# untitled.net
KiCad netlist of a schematic drawn in EAGLE
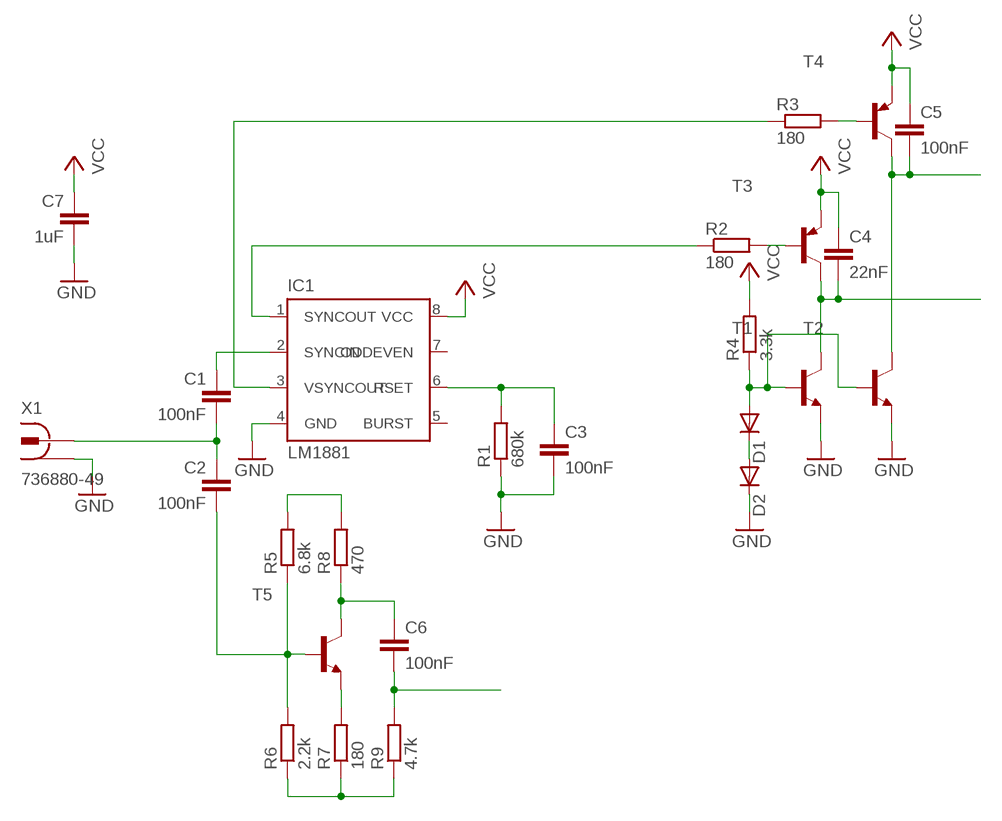
[diagram p0: schematic, sheet 1]

(export (version "E")
  (design (tool "Eeschema 10.0.6"))
  (components
    (comp (ref "C1")
      (value "100nF")
      (footprint "eagle-import:C0805")
      (libsource (lib "eagle-import") (part "C-EUC0805"))
    )
    (comp (ref "C2")
      (value "100nF")
      (footprint "eagle-import:C0805")
      (libsource (lib "eagle-import") (part "C-EUC0805"))
    )
    (comp (ref "C3")
      (value "100nF")
      (footprint "eagle-import:C0805")
      (libsource (lib "eagle-import") (part "C-EUC0805"))
    )
    (comp (ref "C4")
      (value "22nF")
      (footprint "eagle-import:C0805")
      (libsource (lib "eagle-import") (part "C-EUC0805"))
    )
    (comp (ref "C5")
      (value "100nF")
      (footprint "eagle-import:C0805")
      (libsource (lib "eagle-import") (part "C-EUC0805"))
    )
    (comp (ref "C6")
      (value "100nF")
      (footprint "eagle-import:C0805")
      (libsource (lib "eagle-import") (part "C-EUC0805"))
    )
    (comp (ref "C7")
      (value "1uF")
      (footprint "eagle-import:C0805")
      (libsource (lib "eagle-import") (part "C-EUC0805"))
    )
    (comp (ref "D1")
      (value "DIODE-MELF-MLL41")
      (footprint "eagle-import:MELF-MLL41")
      (libsource (lib "eagle-import") (part "DIODE-MELF-MLL41"))
    )
    (comp (ref "D2")
      (value "DIODE-MELF-MLL41")
      (footprint "eagle-import:MELF-MLL41")
      (libsource (lib "eagle-import") (part "DIODE-MELF-MLL41"))
    )
    (comp (ref "IC1")
      (value "LM1881")
      (footprint "eagle-import:DIL08")
      (libsource (lib "eagle-import") (part "LM1881"))
    )
    (comp (ref "R1")
      (value "680k")
      (footprint "eagle-import:R0805")
      (libsource (lib "eagle-import") (part "R-EU_R0805"))
    )
    (comp (ref "R2")
      (value "180")
      (footprint "eagle-import:R0805")
      (libsource (lib "eagle-import") (part "R-EU_R0805"))
    )
    (comp (ref "R3")
      (value "180")
      (footprint "eagle-import:R0805")
      (libsource (lib "eagle-import") (part "R-EU_R0805"))
    )
    (comp (ref "R4")
      (value "3.3k")
      (footprint "eagle-import:R0805")
      (libsource (lib "eagle-import") (part "R-EU_R0805"))
    )
    (comp (ref "R5")
      (value "6.8k")
      (footprint "eagle-import:R0805")
      (libsource (lib "eagle-import") (part "R-EU_R0805"))
    )
    (comp (ref "R6")
      (value "2.2k")
      (footprint "eagle-import:R0805")
      (libsource (lib "eagle-import") (part "R-EU_R0805"))
    )
    (comp (ref "R7")
      (value "180")
      (footprint "eagle-import:R0805")
      (libsource (lib "eagle-import") (part "R-EU_R0805"))
    )
    (comp (ref "R8")
      (value "470")
      (footprint "eagle-import:R0805")
      (libsource (lib "eagle-import") (part "R-EU_R0805"))
    )
    (comp (ref "R9")
      (value "4.7k")
      (footprint "eagle-import:R0805")
      (libsource (lib "eagle-import") (part "R-EU_R0805"))
    )
    (comp (ref "T1")
      (value "-NPN-SOT23-EBC")
      (footprint "eagle-import:SOT23-EBC")
      (libsource (lib "eagle-import") (part "-NPN-SOT23-EBC"))
    )
    (comp (ref "T2")
      (value "-NPN-SOT23-EBC")
      (footprint "eagle-import:SOT23-EBC")
      (libsource (lib "eagle-import") (part "-NPN-SOT23-EBC"))
    )
    (comp (ref "T3")
      (value "-PNP-SOT23-BCE")
      (footprint "eagle-import:SOT23-BCE")
      (libsource (lib "eagle-import") (part "-PNP-SOT23-BCE"))
    )
    (comp (ref "T4")
      (value "-PNP-SOT23-BCE")
      (footprint "eagle-import:SOT23-BCE")
      (libsource (lib "eagle-import") (part "-PNP-SOT23-BCE"))
    )
    (comp (ref "T5")
      (value "-NPN-SOT23-EBC")
      (footprint "eagle-import:SOT23-EBC")
      (libsource (lib "eagle-import") (part "-NPN-SOT23-EBC"))
    )
    (comp (ref "X1")
      (value "736880-49")
      (footprint "eagle-import:736880-49")
      (libsource (lib "eagle-import") (part "736880-49"))
    )
  )
  (nets
    (net (code "1") (name "GND") (class "Default")
      (node (ref "C3") (pin "2") (pinfunction "2_2") (pintype "passive"))
      (node (ref "C7") (pin "2") (pinfunction "2_2") (pintype "passive"))
      (node (ref "D2") (pin "C") (pinfunction "C_C") (pintype "passive"))
      (node (ref "IC1") (pin "4") (pinfunction "GND_4") (pintype "power_in"))
      (node (ref "R1") (pin "1") (pinfunction "1_1") (pintype "passive"))
      (node (ref "T1") (pin "E") (pinfunction "E_E") (pintype "passive"))
      (node (ref "T2") (pin "E") (pinfunction "E_E") (pintype "passive"))
      (node (ref "X1") (pin "1") (pinfunction "1_1") (pintype "passive"))
      (node (ref "X1") (pin "1@1") (pinfunction "1_1@1") (pintype "passive"))
      (node (ref "X1") (pin "1@2") (pinfunction "1_1@2") (pintype "passive"))
    )
    (net (code "2") (name "Net-(C1-Pad2)") (class "Default")
      (node (ref "C1") (pin "2") (pinfunction "2_2") (pintype "passive"))
      (node (ref "C2") (pin "1") (pinfunction "1_1") (pintype "passive"))
      (node (ref "X1") (pin "2") (pinfunction "2_2") (pintype "passive"))
    )
    (net (code "3") (name "Net-(C2-Pad2)") (class "Default")
      (node (ref "C2") (pin "2") (pinfunction "2_2") (pintype "passive"))
      (node (ref "R5") (pin "1") (pinfunction "1_1") (pintype "passive"))
      (node (ref "R6") (pin "2") (pinfunction "2_2") (pintype "passive"))
      (node (ref "T5") (pin "B") (pinfunction "B_B") (pintype "passive"))
    )
    (net (code "4") (name "Net-(C4-Pad2)") (class "Default")
      (node (ref "C4") (pin "2") (pinfunction "2_2") (pintype "passive"))
      (node (ref "T1") (pin "C") (pinfunction "C_C") (pintype "passive"))
      (node (ref "T3") (pin "C") (pinfunction "C_C") (pintype "passive"))
    )
    (net (code "5") (name "Net-(C5-Pad2)") (class "Default")
      (node (ref "C5") (pin "2") (pinfunction "2_2") (pintype "passive"))
      (node (ref "T2") (pin "C") (pinfunction "C_C") (pintype "passive"))
      (node (ref "T4") (pin "C") (pinfunction "C_C") (pintype "passive"))
    )
    (net (code "6") (name "Net-(C6-Pad1)") (class "Default")
      (node (ref "C6") (pin "1") (pinfunction "1_1") (pintype "passive"))
      (node (ref "R8") (pin "1") (pinfunction "1_1") (pintype "passive"))
      (node (ref "T5") (pin "C") (pinfunction "C_C") (pintype "passive"))
    )
    (net (code "7") (name "Net-(C6-Pad2)") (class "Default")
      (node (ref "C6") (pin "2") (pinfunction "2_2") (pintype "passive"))
      (node (ref "R9") (pin "2") (pinfunction "2_2") (pintype "passive"))
    )
    (net (code "8") (name "Net-(D1-PadA)") (class "Default")
      (node (ref "D1") (pin "A") (pinfunction "A_A") (pintype "passive"))
      (node (ref "R4") (pin "1") (pinfunction "1_1") (pintype "passive"))
      (node (ref "T1") (pin "B") (pinfunction "B_B") (pintype "passive"))
      (node (ref "T2") (pin "B") (pinfunction "B_B") (pintype "passive"))
    )
    (net (code "9") (name "Net-(D1-PadC)") (class "Default")
      (node (ref "D1") (pin "C") (pinfunction "C_C") (pintype "passive"))
      (node (ref "D2") (pin "A") (pinfunction "A_A") (pintype "passive"))
    )
    (net (code "10") (name "Net-(IC1-RSET)") (class "Default")
      (node (ref "C3") (pin "1") (pinfunction "1_1") (pintype "passive"))
      (node (ref "IC1") (pin "6") (pinfunction "RSET_6") (pintype "output"))
      (node (ref "R1") (pin "2") (pinfunction "2_2") (pintype "passive"))
    )
    (net (code "11") (name "Net-(IC1-SYNCIN)") (class "Default")
      (node (ref "C1") (pin "1") (pinfunction "1_1") (pintype "passive"))
      (node (ref "IC1") (pin "2") (pinfunction "SYNCIN_2") (pintype "input"))
    )
    (net (code "12") (name "Net-(IC1-SYNCOUT)") (class "Default")
      (node (ref "IC1") (pin "1") (pinfunction "SYNCOUT_1") (pintype "output"))
      (node (ref "R2") (pin "1") (pinfunction "1_1") (pintype "passive"))
    )
    (net (code "13") (name "Net-(IC1-VSYNCOUT)") (class "Default")
      (node (ref "IC1") (pin "3") (pinfunction "VSYNCOUT_3") (pintype "output"))
      (node (ref "R3") (pin "1") (pinfunction "1_1") (pintype "passive"))
    )
    (net (code "14") (name "Net-(R2-Pad2)") (class "Default")
      (node (ref "R2") (pin "2") (pinfunction "2_2") (pintype "passive"))
      (node (ref "T3") (pin "B") (pinfunction "B_B") (pintype "passive"))
    )
    (net (code "15") (name "Net-(R3-Pad2)") (class "Default")
      (node (ref "R3") (pin "2") (pinfunction "2_2") (pintype "passive"))
      (node (ref "T4") (pin "B") (pinfunction "B_B") (pintype "passive"))
    )
    (net (code "16") (name "Net-(R5-Pad2)") (class "Default")
      (node (ref "R5") (pin "2") (pinfunction "2_2") (pintype "passive"))
      (node (ref "R8") (pin "2") (pinfunction "2_2") (pintype "passive"))
    )
    (net (code "17") (name "Net-(R6-Pad1)") (class "Default")
      (node (ref "R6") (pin "1") (pinfunction "1_1") (pintype "passive"))
      (node (ref "R7") (pin "1") (pinfunction "1_1") (pintype "passive"))
      (node (ref "R9") (pin "1") (pinfunction "1_1") (pintype "passive"))
    )
    (net (code "18") (name "Net-(R7-Pad2)") (class "Default")
      (node (ref "R7") (pin "2") (pinfunction "2_2") (pintype "passive"))
      (node (ref "T5") (pin "E") (pinfunction "E_E") (pintype "passive"))
    )
    (net (code "19") (name "VCC") (class "Default")
      (node (ref "C4") (pin "1") (pinfunction "1_1") (pintype "passive"))
      (node (ref "C5") (pin "1") (pinfunction "1_1") (pintype "passive"))
      (node (ref "C7") (pin "1") (pinfunction "1_1") (pintype "passive"))
      (node (ref "IC1") (pin "8") (pinfunction "VCC_8") (pintype "power_in"))
      (node (ref "R4") (pin "2") (pinfunction "2_2") (pintype "passive"))
      (node (ref "T3") (pin "E") (pinfunction "E_E") (pintype "passive"))
      (node (ref "T4") (pin "E") (pinfunction "E_E") (pintype "passive"))
    )
    (net (code "20") (name "unconnected-(IC1-BURST-Pad5)") (class "Default")
      (node (ref "IC1") (pin "5") (pinfunction "BURST_5") (pintype "output"))
    )
    (net (code "21") (name "unconnected-(IC1-ODDEVEN-Pad7)") (class "Default")
      (node (ref "IC1") (pin "7") (pinfunction "ODDEVEN_7") (pintype "output"))
    )
  )
)
